# Adafruit_VL6180_Time_of_Flight_Sensor.net
KiCad netlist of a schematic drawn in EAGLE
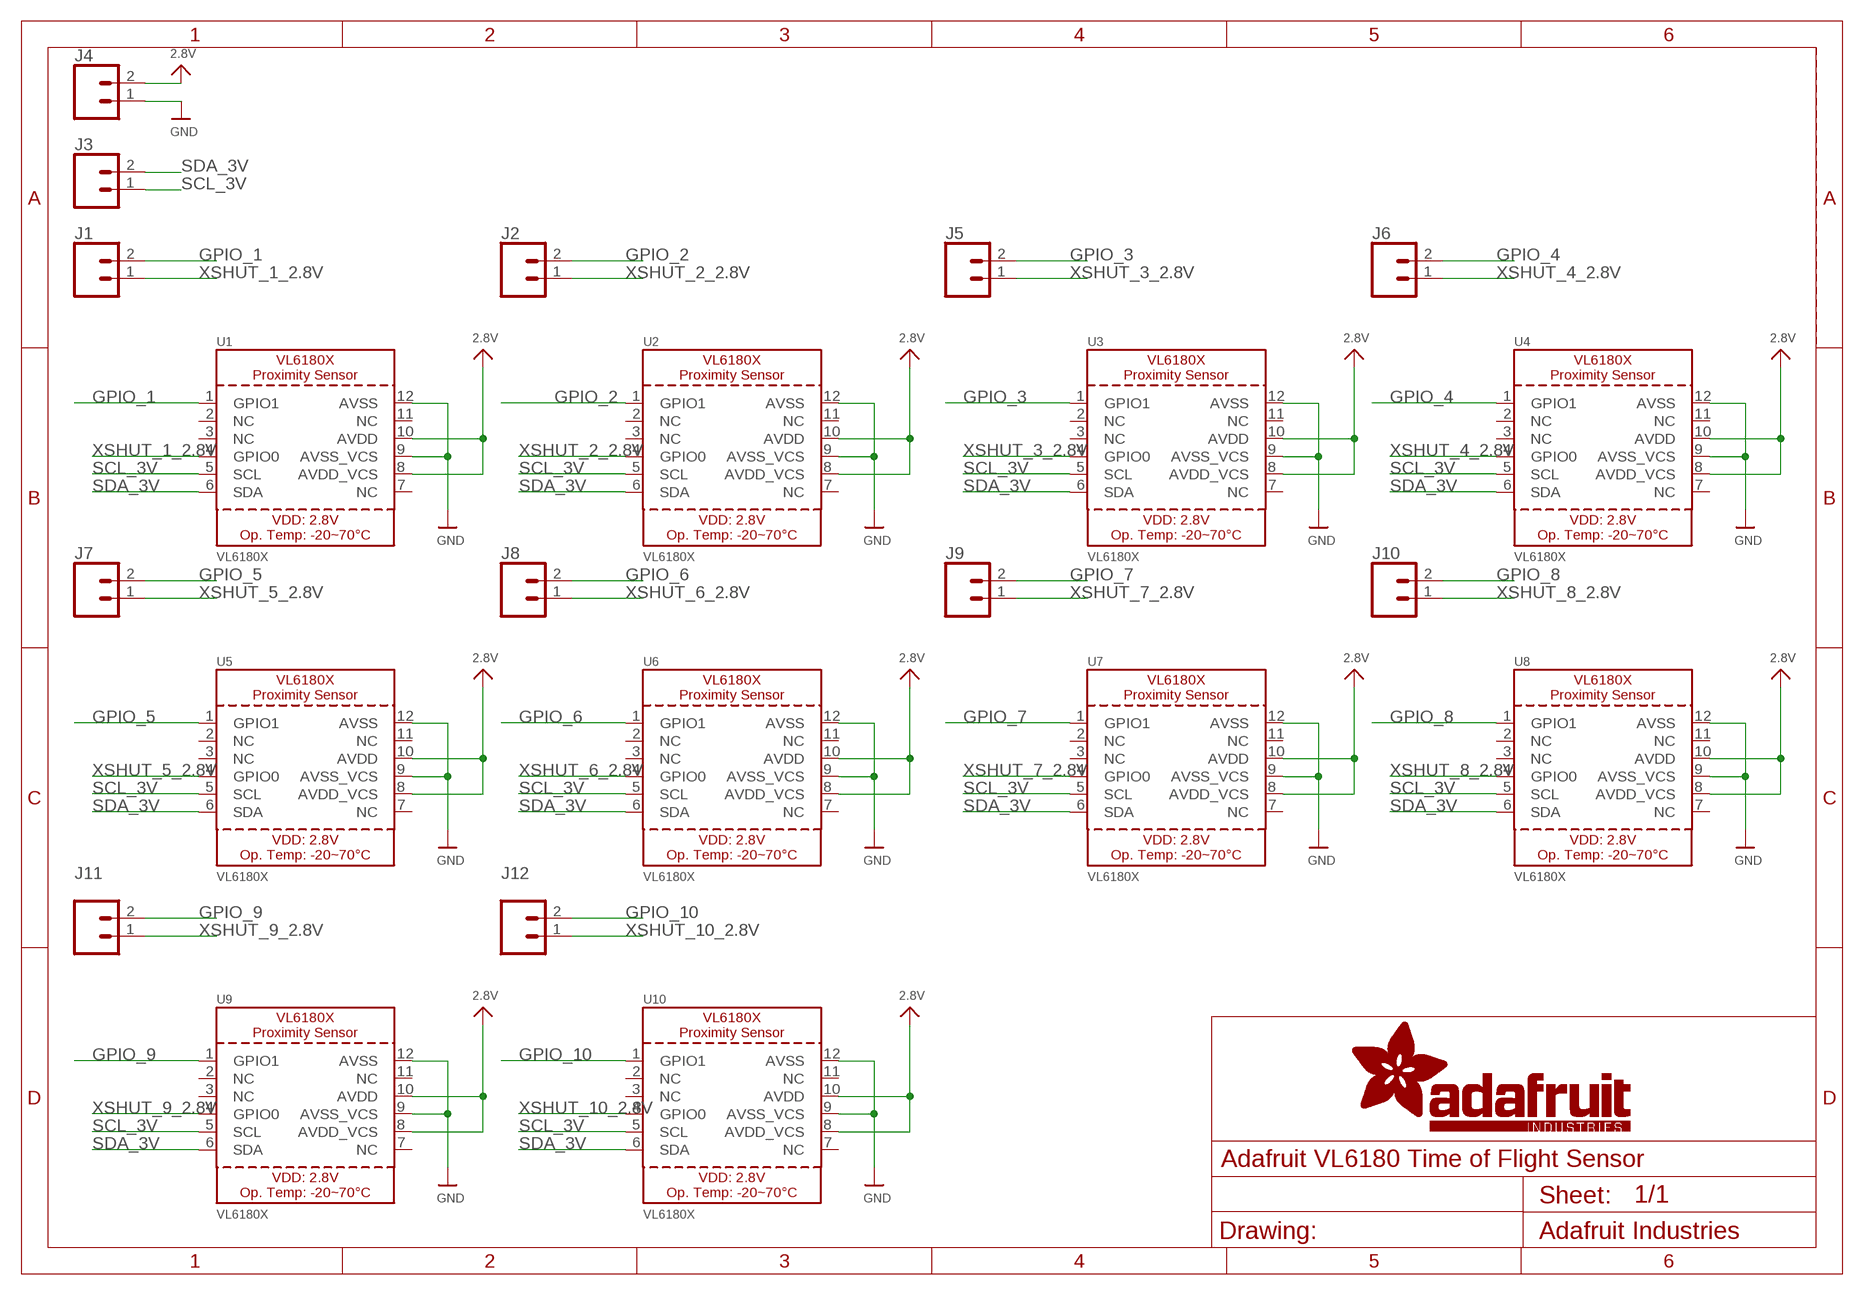
[diagram p0: schematic, sheet 1]

(export (version "E")
  (design (tool "Eeschema 10.0.6"))
  (components
    (comp (ref "J1")
      (value "CONN_021X02_NO_SILK")
      (footprint "eagle-import:1X02_NO_SILK")
      (libsource (lib "eagle-import") (part "CONN_021X02_NO_SILK"))
    )
    (comp (ref "J2")
      (value "CONN_021X02_NO_SILK")
      (footprint "eagle-import:1X02_NO_SILK")
      (libsource (lib "eagle-import") (part "CONN_021X02_NO_SILK"))
    )
    (comp (ref "J3")
      (value "CONN_021X02_NO_SILK")
      (footprint "eagle-import:1X02_NO_SILK")
      (libsource (lib "eagle-import") (part "CONN_021X02_NO_SILK"))
    )
    (comp (ref "J4")
      (value "CONN_021X02_NO_SILK")
      (footprint "eagle-import:1X02_NO_SILK")
      (libsource (lib "eagle-import") (part "CONN_021X02_NO_SILK"))
    )
    (comp (ref "J5")
      (value "CONN_021X02_NO_SILK")
      (footprint "eagle-import:1X02_NO_SILK")
      (libsource (lib "eagle-import") (part "CONN_021X02_NO_SILK"))
    )
    (comp (ref "J6")
      (value "CONN_021X02_NO_SILK")
      (footprint "eagle-import:1X02_NO_SILK")
      (libsource (lib "eagle-import") (part "CONN_021X02_NO_SILK"))
    )
    (comp (ref "J7")
      (value "CONN_021X02_NO_SILK")
      (footprint "eagle-import:1X02_NO_SILK")
      (libsource (lib "eagle-import") (part "CONN_021X02_NO_SILK"))
    )
    (comp (ref "J8")
      (value "CONN_021X02_NO_SILK")
      (footprint "eagle-import:1X02_NO_SILK")
      (libsource (lib "eagle-import") (part "CONN_021X02_NO_SILK"))
    )
    (comp (ref "J9")
      (value "CONN_021X02_NO_SILK")
      (footprint "eagle-import:1X02_NO_SILK")
      (libsource (lib "eagle-import") (part "CONN_021X02_NO_SILK"))
    )
    (comp (ref "J10")
      (value "CONN_021X02_NO_SILK")
      (footprint "eagle-import:1X02_NO_SILK")
      (libsource (lib "eagle-import") (part "CONN_021X02_NO_SILK"))
    )
    (comp (ref "J11")
      (value "CONN_021X02_NO_SILK")
      (footprint "eagle-import:1X02_NO_SILK")
      (libsource (lib "eagle-import") (part "CONN_021X02_NO_SILK"))
    )
    (comp (ref "J12")
      (value "CONN_021X02_NO_SILK")
      (footprint "eagle-import:1X02_NO_SILK")
      (libsource (lib "eagle-import") (part "CONN_021X02_NO_SILK"))
    )
    (comp (ref "U1")
      (value "VL6180X")
      (footprint "eagle-import:VL6180")
      (libsource (lib "eagle-import") (part "VL6180X"))
    )
    (comp (ref "U2")
      (value "VL6180X")
      (footprint "eagle-import:VL6180")
      (libsource (lib "eagle-import") (part "VL6180X"))
    )
    (comp (ref "U3")
      (value "VL6180X")
      (footprint "eagle-import:VL6180")
      (libsource (lib "eagle-import") (part "VL6180X"))
    )
    (comp (ref "U4")
      (value "VL6180X")
      (footprint "eagle-import:VL6180")
      (libsource (lib "eagle-import") (part "VL6180X"))
    )
    (comp (ref "U5")
      (value "VL6180X")
      (footprint "eagle-import:VL6180")
      (libsource (lib "eagle-import") (part "VL6180X"))
    )
    (comp (ref "U6")
      (value "VL6180X")
      (footprint "eagle-import:VL6180")
      (libsource (lib "eagle-import") (part "VL6180X"))
    )
    (comp (ref "U7")
      (value "VL6180X")
      (footprint "eagle-import:VL6180")
      (libsource (lib "eagle-import") (part "VL6180X"))
    )
    (comp (ref "U8")
      (value "VL6180X")
      (footprint "eagle-import:VL6180")
      (libsource (lib "eagle-import") (part "VL6180X"))
    )
    (comp (ref "U9")
      (value "VL6180X")
      (footprint "eagle-import:VL6180")
      (libsource (lib "eagle-import") (part "VL6180X"))
    )
    (comp (ref "U10")
      (value "VL6180X")
      (footprint "eagle-import:VL6180")
      (libsource (lib "eagle-import") (part "VL6180X"))
    )
  )
  (nets
    (net (code "1") (name "/GPIO_1") (class "Default")
      (node (ref "J1") (pin "2") (pinfunction "2_2") (pintype "passive"))
      (node (ref "U1") (pin "1") (pinfunction "GPIO1_1") (pintype "bidirectional"))
    )
    (net (code "2") (name "/GPIO_2") (class "Default")
      (node (ref "J2") (pin "2") (pinfunction "2_2") (pintype "passive"))
      (node (ref "U2") (pin "1") (pinfunction "GPIO1_1") (pintype "bidirectional"))
    )
    (net (code "3") (name "/GPIO_3") (class "Default")
      (node (ref "J5") (pin "2") (pinfunction "2_2") (pintype "passive"))
      (node (ref "U3") (pin "1") (pinfunction "GPIO1_1") (pintype "bidirectional"))
    )
    (net (code "4") (name "/GPIO_4") (class "Default")
      (node (ref "J6") (pin "2") (pinfunction "2_2") (pintype "passive"))
      (node (ref "U4") (pin "1") (pinfunction "GPIO1_1") (pintype "bidirectional"))
    )
    (net (code "5") (name "/GPIO_5") (class "Default")
      (node (ref "J7") (pin "2") (pinfunction "2_2") (pintype "passive"))
      (node (ref "U5") (pin "1") (pinfunction "GPIO1_1") (pintype "bidirectional"))
    )
    (net (code "6") (name "/GPIO_6") (class "Default")
      (node (ref "J8") (pin "2") (pinfunction "2_2") (pintype "passive"))
      (node (ref "U6") (pin "1") (pinfunction "GPIO1_1") (pintype "bidirectional"))
    )
    (net (code "7") (name "/GPIO_7") (class "Default")
      (node (ref "J9") (pin "2") (pinfunction "2_2") (pintype "passive"))
      (node (ref "U7") (pin "1") (pinfunction "GPIO1_1") (pintype "bidirectional"))
    )
    (net (code "8") (name "/GPIO_8") (class "Default")
      (node (ref "J10") (pin "2") (pinfunction "2_2") (pintype "passive"))
      (node (ref "U8") (pin "1") (pinfunction "GPIO1_1") (pintype "bidirectional"))
    )
    (net (code "9") (name "/GPIO_9") (class "Default")
      (node (ref "J11") (pin "2") (pinfunction "2_2") (pintype "passive"))
      (node (ref "U9") (pin "1") (pinfunction "GPIO1_1") (pintype "bidirectional"))
    )
    (net (code "10") (name "/GPIO_10") (class "Default")
      (node (ref "J12") (pin "2") (pinfunction "2_2") (pintype "passive"))
      (node (ref "U10") (pin "1") (pinfunction "GPIO1_1") (pintype "bidirectional"))
    )
    (net (code "11") (name "/SCL_3V") (class "Default")
      (node (ref "J3") (pin "1") (pinfunction "1_1") (pintype "passive"))
      (node (ref "U1") (pin "5") (pinfunction "SCL_5") (pintype "input"))
      (node (ref "U10") (pin "5") (pinfunction "SCL_5") (pintype "input"))
      (node (ref "U2") (pin "5") (pinfunction "SCL_5") (pintype "input"))
      (node (ref "U3") (pin "5") (pinfunction "SCL_5") (pintype "input"))
      (node (ref "U4") (pin "5") (pinfunction "SCL_5") (pintype "input"))
      (node (ref "U5") (pin "5") (pinfunction "SCL_5") (pintype "input"))
      (node (ref "U6") (pin "5") (pinfunction "SCL_5") (pintype "input"))
      (node (ref "U7") (pin "5") (pinfunction "SCL_5") (pintype "input"))
      (node (ref "U8") (pin "5") (pinfunction "SCL_5") (pintype "input"))
      (node (ref "U9") (pin "5") (pinfunction "SCL_5") (pintype "input"))
    )
    (net (code "12") (name "/SDA_3V") (class "Default")
      (node (ref "J3") (pin "2") (pinfunction "2_2") (pintype "passive"))
      (node (ref "U1") (pin "6") (pinfunction "SDA_6") (pintype "bidirectional"))
      (node (ref "U10") (pin "6") (pinfunction "SDA_6") (pintype "bidirectional"))
      (node (ref "U2") (pin "6") (pinfunction "SDA_6") (pintype "bidirectional"))
      (node (ref "U3") (pin "6") (pinfunction "SDA_6") (pintype "bidirectional"))
      (node (ref "U4") (pin "6") (pinfunction "SDA_6") (pintype "bidirectional"))
      (node (ref "U5") (pin "6") (pinfunction "SDA_6") (pintype "bidirectional"))
      (node (ref "U6") (pin "6") (pinfunction "SDA_6") (pintype "bidirectional"))
      (node (ref "U7") (pin "6") (pinfunction "SDA_6") (pintype "bidirectional"))
      (node (ref "U8") (pin "6") (pinfunction "SDA_6") (pintype "bidirectional"))
      (node (ref "U9") (pin "6") (pinfunction "SDA_6") (pintype "bidirectional"))
    )
    (net (code "13") (name "/XSHUT_1_2.8V") (class "Default")
      (node (ref "J1") (pin "1") (pinfunction "1_1") (pintype "passive"))
      (node (ref "U1") (pin "4") (pinfunction "GPIO0_4") (pintype "bidirectional"))
    )
    (net (code "14") (name "/XSHUT_2_2.8V") (class "Default")
      (node (ref "J2") (pin "1") (pinfunction "1_1") (pintype "passive"))
      (node (ref "U2") (pin "4") (pinfunction "GPIO0_4") (pintype "bidirectional"))
    )
    (net (code "15") (name "/XSHUT_3_2.8V") (class "Default")
      (node (ref "J5") (pin "1") (pinfunction "1_1") (pintype "passive"))
      (node (ref "U3") (pin "4") (pinfunction "GPIO0_4") (pintype "bidirectional"))
    )
    (net (code "16") (name "/XSHUT_4_2.8V") (class "Default")
      (node (ref "J6") (pin "1") (pinfunction "1_1") (pintype "passive"))
      (node (ref "U4") (pin "4") (pinfunction "GPIO0_4") (pintype "bidirectional"))
    )
    (net (code "17") (name "/XSHUT_5_2.8V") (class "Default")
      (node (ref "J7") (pin "1") (pinfunction "1_1") (pintype "passive"))
      (node (ref "U5") (pin "4") (pinfunction "GPIO0_4") (pintype "bidirectional"))
    )
    (net (code "18") (name "/XSHUT_6_2.8V") (class "Default")
      (node (ref "J8") (pin "1") (pinfunction "1_1") (pintype "passive"))
      (node (ref "U6") (pin "4") (pinfunction "GPIO0_4") (pintype "bidirectional"))
    )
    (net (code "19") (name "/XSHUT_7_2.8V") (class "Default")
      (node (ref "J9") (pin "1") (pinfunction "1_1") (pintype "passive"))
      (node (ref "U7") (pin "4") (pinfunction "GPIO0_4") (pintype "bidirectional"))
    )
    (net (code "20") (name "/XSHUT_8_2.8V") (class "Default")
      (node (ref "J10") (pin "1") (pinfunction "1_1") (pintype "passive"))
      (node (ref "U8") (pin "4") (pinfunction "GPIO0_4") (pintype "bidirectional"))
    )
    (net (code "21") (name "/XSHUT_9_2.8V") (class "Default")
      (node (ref "J11") (pin "1") (pinfunction "1_1") (pintype "passive"))
      (node (ref "U9") (pin "4") (pinfunction "GPIO0_4") (pintype "bidirectional"))
    )
    (net (code "22") (name "/XSHUT_10_2.8V") (class "Default")
      (node (ref "J12") (pin "1") (pinfunction "1_1") (pintype "passive"))
      (node (ref "U10") (pin "4") (pinfunction "GPIO0_4") (pintype "bidirectional"))
    )
    (net (code "23") (name "2.8V") (class "Default")
      (node (ref "J4") (pin "2") (pinfunction "2_2") (pintype "passive"))
      (node (ref "U1") (pin "10") (pinfunction "AVDD_10") (pintype "power_in"))
      (node (ref "U1") (pin "8") (pinfunction "AVDD_VCS_8") (pintype "power_in"))
      (node (ref "U10") (pin "10") (pinfunction "AVDD_10") (pintype "power_in"))
      (node (ref "U10") (pin "8") (pinfunction "AVDD_VCS_8") (pintype "power_in"))
      (node (ref "U2") (pin "10") (pinfunction "AVDD_10") (pintype "power_in"))
      (node (ref "U2") (pin "8") (pinfunction "AVDD_VCS_8") (pintype "power_in"))
      (node (ref "U3") (pin "10") (pinfunction "AVDD_10") (pintype "power_in"))
      (node (ref "U3") (pin "8") (pinfunction "AVDD_VCS_8") (pintype "power_in"))
      (node (ref "U4") (pin "10") (pinfunction "AVDD_10") (pintype "power_in"))
      (node (ref "U4") (pin "8") (pinfunction "AVDD_VCS_8") (pintype "power_in"))
      (node (ref "U5") (pin "10") (pinfunction "AVDD_10") (pintype "power_in"))
      (node (ref "U5") (pin "8") (pinfunction "AVDD_VCS_8") (pintype "power_in"))
      (node (ref "U6") (pin "10") (pinfunction "AVDD_10") (pintype "power_in"))
      (node (ref "U6") (pin "8") (pinfunction "AVDD_VCS_8") (pintype "power_in"))
      (node (ref "U7") (pin "10") (pinfunction "AVDD_10") (pintype "power_in"))
      (node (ref "U7") (pin "8") (pinfunction "AVDD_VCS_8") (pintype "power_in"))
      (node (ref "U8") (pin "10") (pinfunction "AVDD_10") (pintype "power_in"))
      (node (ref "U8") (pin "8") (pinfunction "AVDD_VCS_8") (pintype "power_in"))
      (node (ref "U9") (pin "10") (pinfunction "AVDD_10") (pintype "power_in"))
      (node (ref "U9") (pin "8") (pinfunction "AVDD_VCS_8") (pintype "power_in"))
    )
    (net (code "24") (name "GND") (class "Default")
      (node (ref "J4") (pin "1") (pinfunction "1_1") (pintype "passive"))
      (node (ref "U1") (pin "12") (pinfunction "AVSS_12") (pintype "power_in"))
      (node (ref "U1") (pin "9") (pinfunction "AVSS_VCS_9") (pintype "power_in"))
      (node (ref "U10") (pin "12") (pinfunction "AVSS_12") (pintype "power_in"))
      (node (ref "U10") (pin "9") (pinfunction "AVSS_VCS_9") (pintype "power_in"))
      (node (ref "U2") (pin "12") (pinfunction "AVSS_12") (pintype "power_in"))
      (node (ref "U2") (pin "9") (pinfunction "AVSS_VCS_9") (pintype "power_in"))
      (node (ref "U3") (pin "12") (pinfunction "AVSS_12") (pintype "power_in"))
      (node (ref "U3") (pin "9") (pinfunction "AVSS_VCS_9") (pintype "power_in"))
      (node (ref "U4") (pin "12") (pinfunction "AVSS_12") (pintype "power_in"))
      (node (ref "U4") (pin "9") (pinfunction "AVSS_VCS_9") (pintype "power_in"))
      (node (ref "U5") (pin "12") (pinfunction "AVSS_12") (pintype "power_in"))
      (node (ref "U5") (pin "9") (pinfunction "AVSS_VCS_9") (pintype "power_in"))
      (node (ref "U6") (pin "12") (pinfunction "AVSS_12") (pintype "power_in"))
      (node (ref "U6") (pin "9") (pinfunction "AVSS_VCS_9") (pintype "power_in"))
      (node (ref "U7") (pin "12") (pinfunction "AVSS_12") (pintype "power_in"))
      (node (ref "U7") (pin "9") (pinfunction "AVSS_VCS_9") (pintype "power_in"))
      (node (ref "U8") (pin "12") (pinfunction "AVSS_12") (pintype "power_in"))
      (node (ref "U8") (pin "9") (pinfunction "AVSS_VCS_9") (pintype "power_in"))
      (node (ref "U9") (pin "12") (pinfunction "AVSS_12") (pintype "power_in"))
      (node (ref "U9") (pin "9") (pinfunction "AVSS_VCS_9") (pintype "power_in"))
    )
    (net (code "25") (name "unconnected-(U1-NC-Pad2)") (class "Default")
      (node (ref "U1") (pin "2") (pinfunction "NC_2") (pintype "no_connect"))
    )
    (net (code "26") (name "unconnected-(U1-NC-Pad3)") (class "Default")
      (node (ref "U1") (pin "3") (pinfunction "NC_3") (pintype "no_connect"))
    )
    (net (code "27") (name "unconnected-(U1-NC-Pad7)") (class "Default")
      (node (ref "U1") (pin "7") (pinfunction "NC_7") (pintype "no_connect"))
    )
    (net (code "28") (name "unconnected-(U1-NC-Pad11)") (class "Default")
      (node (ref "U1") (pin "11") (pinfunction "NC_11") (pintype "no_connect"))
    )
    (net (code "29") (name "unconnected-(U2-NC-Pad2)") (class "Default")
      (node (ref "U2") (pin "2") (pinfunction "NC_2") (pintype "no_connect"))
    )
    (net (code "30") (name "unconnected-(U2-NC-Pad3)") (class "Default")
      (node (ref "U2") (pin "3") (pinfunction "NC_3") (pintype "no_connect"))
    )
    (net (code "31") (name "unconnected-(U2-NC-Pad7)") (class "Default")
      (node (ref "U2") (pin "7") (pinfunction "NC_7") (pintype "no_connect"))
    )
    (net (code "32") (name "unconnected-(U2-NC-Pad11)") (class "Default")
      (node (ref "U2") (pin "11") (pinfunction "NC_11") (pintype "no_connect"))
    )
    (net (code "33") (name "unconnected-(U3-NC-Pad2)") (class "Default")
      (node (ref "U3") (pin "2") (pinfunction "NC_2") (pintype "no_connect"))
    )
    (net (code "34") (name "unconnected-(U3-NC-Pad3)") (class "Default")
      (node (ref "U3") (pin "3") (pinfunction "NC_3") (pintype "no_connect"))
    )
    (net (code "35") (name "unconnected-(U3-NC-Pad7)") (class "Default")
      (node (ref "U3") (pin "7") (pinfunction "NC_7") (pintype "no_connect"))
    )
    (net (code "36") (name "unconnected-(U3-NC-Pad11)") (class "Default")
      (node (ref "U3") (pin "11") (pinfunction "NC_11") (pintype "no_connect"))
    )
    (net (code "37") (name "unconnected-(U4-NC-Pad2)") (class "Default")
      (node (ref "U4") (pin "2") (pinfunction "NC_2") (pintype "no_connect"))
    )
    (net (code "38") (name "unconnected-(U4-NC-Pad3)") (class "Default")
      (node (ref "U4") (pin "3") (pinfunction "NC_3") (pintype "no_connect"))
    )
    (net (code "39") (name "unconnected-(U4-NC-Pad7)") (class "Default")
      (node (ref "U4") (pin "7") (pinfunction "NC_7") (pintype "no_connect"))
    )
    (net (code "40") (name "unconnected-(U4-NC-Pad11)") (class "Default")
      (node (ref "U4") (pin "11") (pinfunction "NC_11") (pintype "no_connect"))
    )
    (net (code "41") (name "unconnected-(U5-NC-Pad2)") (class "Default")
      (node (ref "U5") (pin "2") (pinfunction "NC_2") (pintype "no_connect"))
    )
    (net (code "42") (name "unconnected-(U5-NC-Pad3)") (class "Default")
      (node (ref "U5") (pin "3") (pinfunction "NC_3") (pintype "no_connect"))
    )
    (net (code "43") (name "unconnected-(U5-NC-Pad7)") (class "Default")
      (node (ref "U5") (pin "7") (pinfunction "NC_7") (pintype "no_connect"))
    )
    (net (code "44") (name "unconnected-(U5-NC-Pad11)") (class "Default")
      (node (ref "U5") (pin "11") (pinfunction "NC_11") (pintype "no_connect"))
    )
    (net (code "45") (name "unconnected-(U6-NC-Pad2)") (class "Default")
      (node (ref "U6") (pin "2") (pinfunction "NC_2") (pintype "no_connect"))
    )
    (net (code "46") (name "unconnected-(U6-NC-Pad3)") (class "Default")
      (node (ref "U6") (pin "3") (pinfunction "NC_3") (pintype "no_connect"))
    )
    (net (code "47") (name "unconnected-(U6-NC-Pad7)") (class "Default")
      (node (ref "U6") (pin "7") (pinfunction "NC_7") (pintype "no_connect"))
    )
    (net (code "48") (name "unconnected-(U6-NC-Pad11)") (class "Default")
      (node (ref "U6") (pin "11") (pinfunction "NC_11") (pintype "no_connect"))
    )
    (net (code "49") (name "unconnected-(U7-NC-Pad2)") (class "Default")
      (node (ref "U7") (pin "2") (pinfunction "NC_2") (pintype "no_connect"))
    )
    (net (code "50") (name "unconnected-(U7-NC-Pad3)") (class "Default")
      (node (ref "U7") (pin "3") (pinfunction "NC_3") (pintype "no_connect"))
    )
    (net (code "51") (name "unconnected-(U7-NC-Pad7)") (class "Default")
      (node (ref "U7") (pin "7") (pinfunction "NC_7") (pintype "no_connect"))
    )
    (net (code "52") (name "unconnected-(U7-NC-Pad11)") (class "Default")
      (node (ref "U7") (pin "11") (pinfunction "NC_11") (pintype "no_connect"))
    )
    (net (code "53") (name "unconnected-(U8-NC-Pad2)") (class "Default")
      (node (ref "U8") (pin "2") (pinfunction "NC_2") (pintype "no_connect"))
    )
    (net (code "54") (name "unconnected-(U8-NC-Pad3)") (class "Default")
      (node (ref "U8") (pin "3") (pinfunction "NC_3") (pintype "no_connect"))
    )
    (net (code "55") (name "unconnected-(U8-NC-Pad7)") (class "Default")
      (node (ref "U8") (pin "7") (pinfunction "NC_7") (pintype "no_connect"))
    )
    (net (code "56") (name "unconnected-(U8-NC-Pad11)") (class "Default")
      (node (ref "U8") (pin "11") (pinfunction "NC_11") (pintype "no_connect"))
    )
    (net (code "57") (name "unconnected-(U9-NC-Pad2)") (class "Default")
      (node (ref "U9") (pin "2") (pinfunction "NC_2") (pintype "no_connect"))
    )
    (net (code "58") (name "unconnected-(U9-NC-Pad3)") (class "Default")
      (node (ref "U9") (pin "3") (pinfunction "NC_3") (pintype "no_connect"))
    )
    (net (code "59") (name "unconnected-(U9-NC-Pad7)") (class "Default")
      (node (ref "U9") (pin "7") (pinfunction "NC_7") (pintype "no_connect"))
    )
    (net (code "60") (name "unconnected-(U9-NC-Pad11)") (class "Default")
      (node (ref "U9") (pin "11") (pinfunction "NC_11") (pintype "no_connect"))
    )
    (net (code "61") (name "unconnected-(U10-NC-Pad2)") (class "Default")
      (node (ref "U10") (pin "2") (pinfunction "NC_2") (pintype "no_connect"))
    )
    (net (code "62") (name "unconnected-(U10-NC-Pad3)") (class "Default")
      (node (ref "U10") (pin "3") (pinfunction "NC_3") (pintype "no_connect"))
    )
    (net (code "63") (name "unconnected-(U10-NC-Pad7)") (class "Default")
      (node (ref "U10") (pin "7") (pinfunction "NC_7") (pintype "no_connect"))
    )
    (net (code "64") (name "unconnected-(U10-NC-Pad11)") (class "Default")
      (node (ref "U10") (pin "11") (pinfunction "NC_11") (pintype "no_connect"))
    )
  )
)
